# board.net
KiCad netlist of a schematic drawn in EAGLE
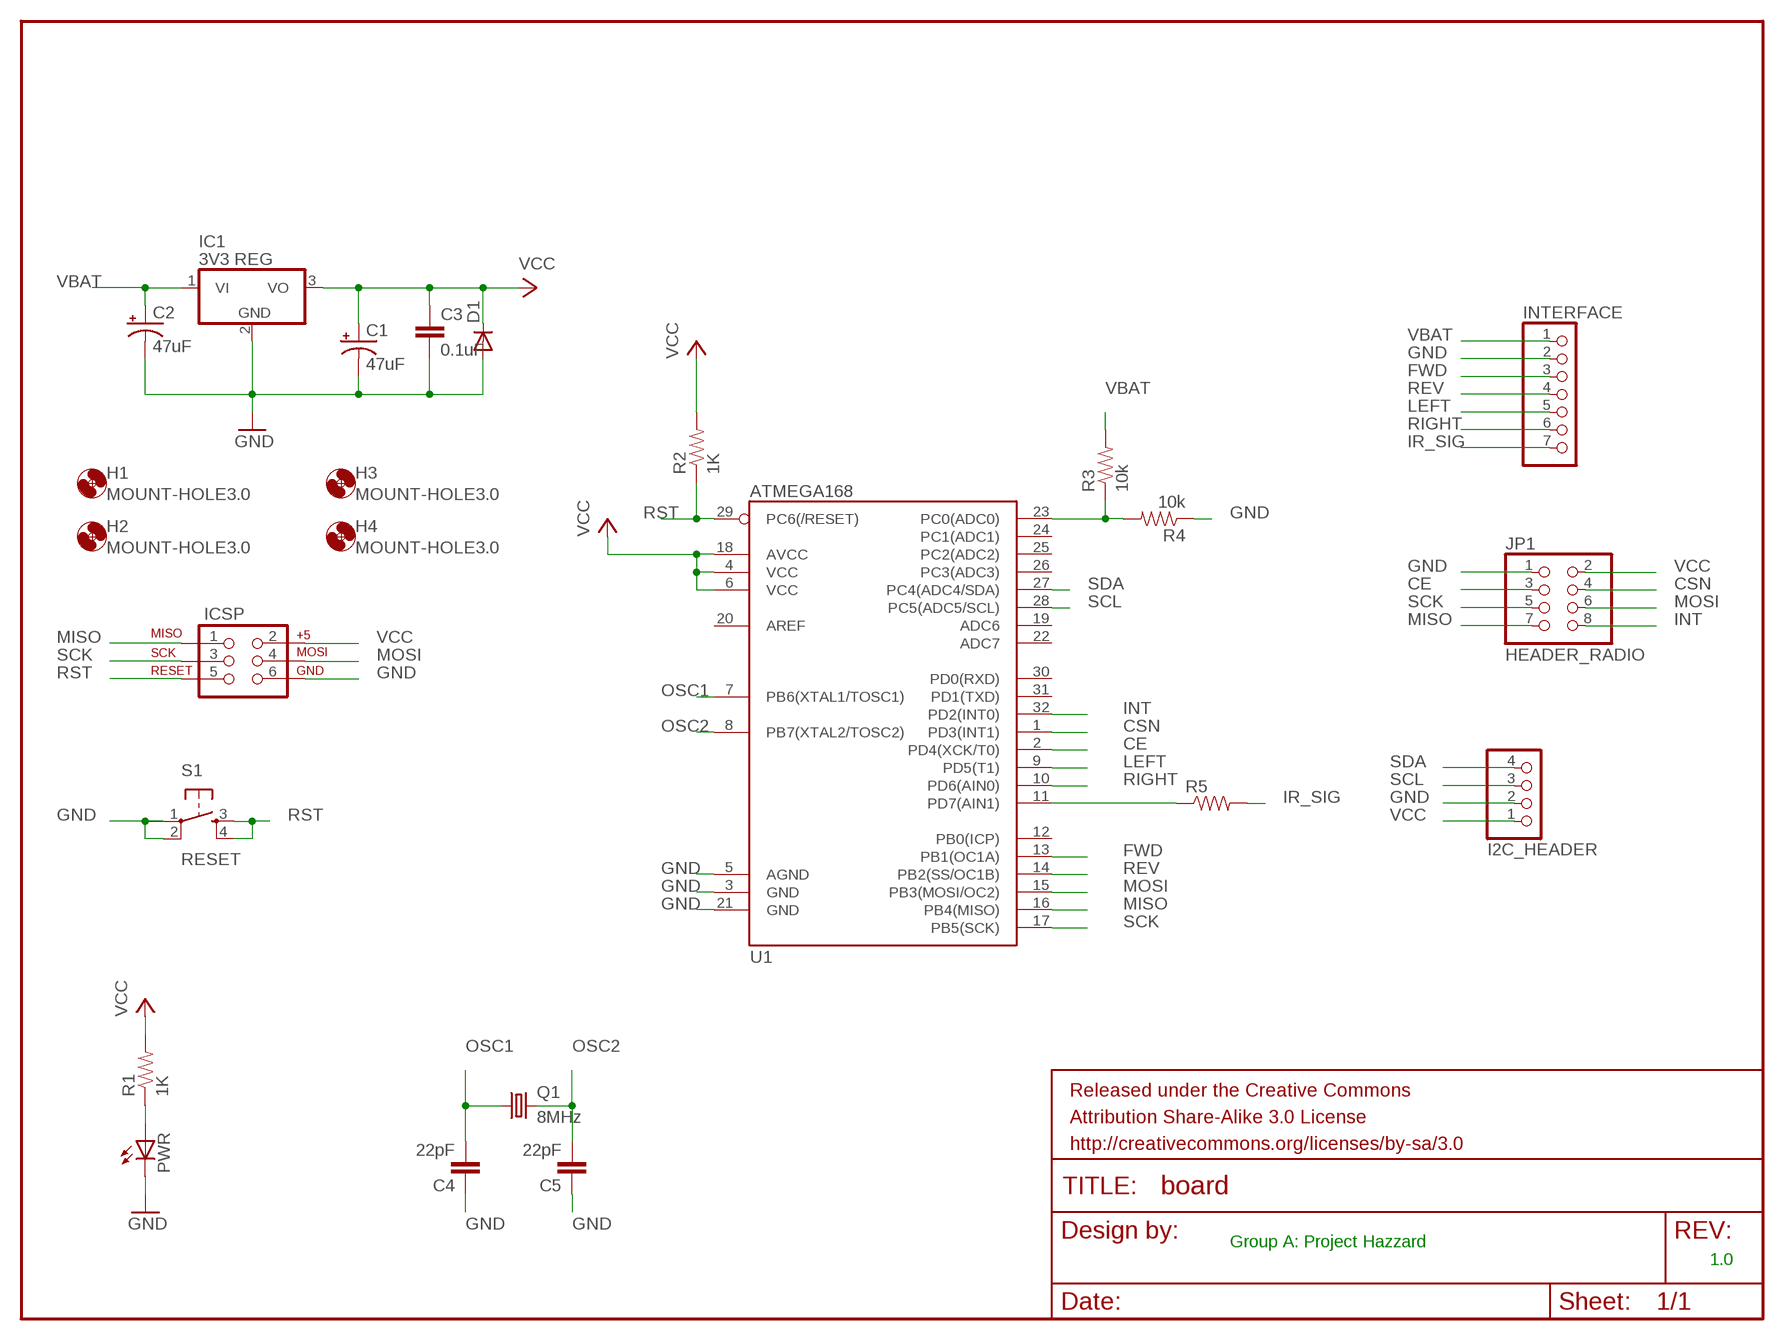
[diagram p0: schematic, sheet 1]

(export (version "E")
  (design (tool "Eeschema 10.0.6"))
  (components
    (comp (ref "C1")
      (value "47uF")
      (footprint "eagle-import:CPOL-RADIAL-100UF-25V")
      (libsource (lib "eagle-import") (part "CAP_POLPTH1"))
    )
    (comp (ref "C2")
      (value "47uF")
      (footprint "eagle-import:CPOL-RADIAL-100UF-25V")
      (libsource (lib "eagle-import") (part "CAP_POLPTH1"))
    )
    (comp (ref "C3")
      (value "0.1uF")
      (footprint "eagle-import:CAP-PTH-SMALL-KIT")
      (libsource (lib "eagle-import") (part "CAPKIT"))
    )
    (comp (ref "C4")
      (value "22pF")
      (footprint "eagle-import:CAP-PTH-SMALL")
      (libsource (lib "eagle-import") (part "CAPPTH"))
    )
    (comp (ref "C5")
      (value "22pF")
      (footprint "eagle-import:CAP-PTH-SMALL")
      (libsource (lib "eagle-import") (part "CAPPTH"))
    )
    (comp (ref "D1")
      (value "DIODEPTH")
      (footprint "eagle-import:DIODE-1N4001")
      (libsource (lib "eagle-import") (part "DIODEPTH"))
    )
    (comp (ref "FRAME1")
      (value "FRAME-LETTER")
      (footprint "eagle-import:CREATIVE_COMMONS")
      (libsource (lib "eagle-import") (part "FRAME-LETTER"))
    )
    (comp (ref "H1")
      (value "MOUNT-HOLE3.0")
      (footprint "eagle-import:3,0")
      (libsource (lib "eagle-import") (part "MOUNT-HOLE3.0"))
    )
    (comp (ref "H2")
      (value "MOUNT-HOLE3.0")
      (footprint "eagle-import:3,0")
      (libsource (lib "eagle-import") (part "MOUNT-HOLE3.0"))
    )
    (comp (ref "H3")
      (value "MOUNT-HOLE3.0")
      (footprint "eagle-import:3,0")
      (libsource (lib "eagle-import") (part "MOUNT-HOLE3.0"))
    )
    (comp (ref "H4")
      (value "MOUNT-HOLE3.0")
      (footprint "eagle-import:3,0")
      (libsource (lib "eagle-import") (part "MOUNT-HOLE3.0"))
    )
    (comp (ref "I2C_HEADER")
      (value "PINHD-1X4")
      (footprint "eagle-import:1X04")
      (libsource (lib "eagle-import") (part "PINHD-1X4"))
    )
    (comp (ref "IC1")
      (value "3V3 REG")
      (footprint "eagle-import:TO220V")
      (libsource (lib "eagle-import") (part "78TV6"))
    )
    (comp (ref "ICSP")
      (value "AVR_SPI_PRG_6PTH")
      (footprint "eagle-import:2X3")
      (libsource (lib "eagle-import") (part "AVR_SPI_PRG_6PTH"))
    )
    (comp (ref "INTERFACE")
      (value "PINHD-1X7")
      (footprint "eagle-import:1X07")
      (libsource (lib "eagle-import") (part "PINHD-1X7"))
    )
    (comp (ref "JP1")
      (value "HEADER_RADIO")
      (footprint "eagle-import:2X04")
      (libsource (lib "eagle-import") (part "PINHD-2X4"))
    )
    (comp (ref "PWR")
      (value "LED5MM")
      (footprint "eagle-import:LED5MM")
      (libsource (lib "eagle-import") (part "LED5MM"))
    )
    (comp (ref "Q1")
      (value "8MHz")
      (footprint "eagle-import:HC49_S")
      (libsource (lib "eagle-import") (part "CRYSTALHC49S"))
    )
    (comp (ref "R1")
      (value "1K")
      (footprint "eagle-import:AXIAL-0.4")
      (libsource (lib "eagle-import") (part "RESISTORPTH-1/4W"))
    )
    (comp (ref "R2")
      (value "1K")
      (footprint "eagle-import:AXIAL-0.4")
      (libsource (lib "eagle-import") (part "RESISTORPTH-1/4W"))
    )
    (comp (ref "R3")
      (value "10k")
      (footprint "eagle-import:AXIAL-0.4")
      (libsource (lib "eagle-import") (part "SparkFun-Passives_RESISTORPTH-1/4W"))
    )
    (comp (ref "R4")
      (value "10k")
      (footprint "eagle-import:AXIAL-0.4")
      (libsource (lib "eagle-import") (part "SparkFun-Passives_RESISTORPTH-1/4W"))
    )
    (comp (ref "R5")
      (value "RESISTORPTH-1/4W")
      (footprint "eagle-import:AXIAL-0.4")
      (libsource (lib "eagle-import") (part "SparkFun-Passives_RESISTORPTH-1/4W"))
    )
    (comp (ref "S1")
      (value "RESET")
      (footprint "eagle-import:TACTILE-PTH")
      (libsource (lib "eagle-import") (part "TAC_SWITCHPTH"))
    )
    (comp (ref "U1")
      (value "ATMEGA168")
      (footprint "eagle-import:TQFP32-08")
      (libsource (lib "eagle-import") (part "ATMEGA168"))
    )
  )
  (nets
    (net (code "1") (name "/CE") (class "Default")
      (node (ref "JP1") (pin "3") (pinfunction "3_3") (pintype "passive"))
      (node (ref "U1") (pin "2") (pinfunction "PD4(XCK/T0)_2") (pintype "bidirectional"))
    )
    (net (code "2") (name "/CSN") (class "Default")
      (node (ref "JP1") (pin "4") (pinfunction "4_4") (pintype "passive"))
      (node (ref "U1") (pin "1") (pinfunction "PD3(INT1)_1") (pintype "bidirectional"))
    )
    (net (code "3") (name "/FWD") (class "Default")
      (node (ref "INTERFACE") (pin "3") (pinfunction "3_3") (pintype "passive"))
      (node (ref "U1") (pin "13") (pinfunction "PB1(OC1A)_13") (pintype "bidirectional"))
    )
    (net (code "4") (name "/INT") (class "Default")
      (node (ref "JP1") (pin "8") (pinfunction "8_8") (pintype "passive"))
      (node (ref "U1") (pin "32") (pinfunction "PD2(INT0)_32") (pintype "bidirectional"))
    )
    (net (code "5") (name "/IR_SIG") (class "Default")
      (node (ref "INTERFACE") (pin "7") (pinfunction "7_7") (pintype "passive"))
      (node (ref "R5") (pin "P$2") (pinfunction "2_P$2") (pintype "passive"))
    )
    (net (code "6") (name "/LEFT") (class "Default")
      (node (ref "INTERFACE") (pin "5") (pinfunction "5_5") (pintype "passive"))
      (node (ref "U1") (pin "9") (pinfunction "PD5(T1)_9") (pintype "bidirectional"))
    )
    (net (code "7") (name "/MISO") (class "Default")
      (node (ref "ICSP") (pin "1") (pinfunction "1_1") (pintype "passive"))
      (node (ref "JP1") (pin "7") (pinfunction "7_7") (pintype "passive"))
      (node (ref "U1") (pin "16") (pinfunction "PB4(MISO)_16") (pintype "bidirectional"))
    )
    (net (code "8") (name "/MOSI") (class "Default")
      (node (ref "ICSP") (pin "4") (pinfunction "4_4") (pintype "passive"))
      (node (ref "JP1") (pin "6") (pinfunction "6_6") (pintype "passive"))
      (node (ref "U1") (pin "15") (pinfunction "PB3(MOSI/OC2)_15") (pintype "bidirectional"))
    )
    (net (code "9") (name "/OSC1") (class "Default")
      (node (ref "C4") (pin "2") (pinfunction "2_2") (pintype "passive"))
      (node (ref "Q1") (pin "1") (pinfunction "1_1") (pintype "passive"))
      (node (ref "U1") (pin "7") (pinfunction "PB6(XTAL1/TOSC1)_7") (pintype "bidirectional"))
    )
    (net (code "10") (name "/OSC2") (class "Default")
      (node (ref "C5") (pin "2") (pinfunction "2_2") (pintype "passive"))
      (node (ref "Q1") (pin "2") (pinfunction "2_2") (pintype "passive"))
      (node (ref "U1") (pin "8") (pinfunction "PB7(XTAL2/TOSC2)_8") (pintype "bidirectional"))
    )
    (net (code "11") (name "/REV") (class "Default")
      (node (ref "INTERFACE") (pin "4") (pinfunction "4_4") (pintype "passive"))
      (node (ref "U1") (pin "14") (pinfunction "PB2(SS/OC1B)_14") (pintype "bidirectional"))
    )
    (net (code "12") (name "/RIGHT") (class "Default")
      (node (ref "INTERFACE") (pin "6") (pinfunction "6_6") (pintype "passive"))
      (node (ref "U1") (pin "10") (pinfunction "PD6(AIN0)_10") (pintype "bidirectional"))
    )
    (net (code "13") (name "/RST") (class "Default")
      (node (ref "ICSP") (pin "5") (pinfunction "5_5") (pintype "passive"))
      (node (ref "R2") (pin "P$1") (pinfunction "1_P$1") (pintype "passive"))
      (node (ref "S1") (pin "3") (pinfunction "3_3") (pintype "passive"))
      (node (ref "S1") (pin "4") (pinfunction "4_4") (pintype "passive"))
      (node (ref "U1") (pin "29") (pinfunction "PC6(/RESET)_29") (pintype "bidirectional"))
    )
    (net (code "14") (name "/SCK") (class "Default")
      (node (ref "ICSP") (pin "3") (pinfunction "3_3") (pintype "passive"))
      (node (ref "JP1") (pin "5") (pinfunction "5_5") (pintype "passive"))
      (node (ref "U1") (pin "17") (pinfunction "PB5(SCK)_17") (pintype "bidirectional"))
    )
    (net (code "15") (name "/SCL") (class "Default")
      (node (ref "I2C_HEADER") (pin "3") (pinfunction "3_3") (pintype "passive"))
      (node (ref "U1") (pin "28") (pinfunction "PC5(ADC5/SCL)_28") (pintype "bidirectional"))
    )
    (net (code "16") (name "/SDA") (class "Default")
      (node (ref "I2C_HEADER") (pin "4") (pinfunction "4_4") (pintype "passive"))
      (node (ref "U1") (pin "27") (pinfunction "PC4(ADC4/SDA)_27") (pintype "bidirectional"))
    )
    (net (code "17") (name "/VBAT") (class "Default")
      (node (ref "C2") (pin "1") (pinfunction "+_1") (pintype "passive"))
      (node (ref "IC1") (pin "1") (pinfunction "VI_1") (pintype "input"))
      (node (ref "INTERFACE") (pin "1") (pinfunction "1_1") (pintype "passive"))
      (node (ref "R3") (pin "P$2") (pinfunction "2_P$2") (pintype "passive"))
    )
    (net (code "18") (name "GND") (class "Default")
      (node (ref "C1") (pin "2") (pinfunction "-_2") (pintype "passive"))
      (node (ref "C2") (pin "2") (pinfunction "-_2") (pintype "passive"))
      (node (ref "C3") (pin "2") (pinfunction "2_2") (pintype "passive"))
      (node (ref "C4") (pin "1") (pinfunction "1_1") (pintype "passive"))
      (node (ref "C5") (pin "1") (pinfunction "1_1") (pintype "passive"))
      (node (ref "D1") (pin "A") (pinfunction "A_A") (pintype "passive"))
      (node (ref "I2C_HEADER") (pin "2") (pinfunction "2_2") (pintype "passive"))
      (node (ref "IC1") (pin "2") (pinfunction "GND_2") (pintype "passive"))
      (node (ref "ICSP") (pin "6") (pinfunction "6_6") (pintype "passive"))
      (node (ref "INTERFACE") (pin "2") (pinfunction "2_2") (pintype "passive"))
      (node (ref "JP1") (pin "1") (pinfunction "1_1") (pintype "passive"))
      (node (ref "PWR") (pin "K") (pinfunction "C_K") (pintype "passive"))
      (node (ref "R4") (pin "P$1") (pinfunction "1_P$1") (pintype "passive"))
      (node (ref "S1") (pin "1") (pinfunction "1_1") (pintype "passive"))
      (node (ref "S1") (pin "2") (pinfunction "2_2") (pintype "passive"))
      (node (ref "U1") (pin "21") (pinfunction "GND_21") (pintype "bidirectional"))
      (node (ref "U1") (pin "3") (pinfunction "GND_3") (pintype "bidirectional"))
      (node (ref "U1") (pin "5") (pinfunction "AGND_5") (pintype "bidirectional"))
    )
    (net (code "19") (name "Net-(R1-1)") (class "Default")
      (node (ref "PWR") (pin "A") (pinfunction "A_A") (pintype "passive"))
      (node (ref "R1") (pin "P$1") (pinfunction "1_P$1") (pintype "passive"))
    )
    (net (code "20") (name "Net-(R3-1)") (class "Default")
      (node (ref "R3") (pin "P$1") (pinfunction "1_P$1") (pintype "passive"))
      (node (ref "R4") (pin "P$2") (pinfunction "2_P$2") (pintype "passive"))
      (node (ref "U1") (pin "23") (pinfunction "PC0(ADC0)_23") (pintype "bidirectional"))
    )
    (net (code "21") (name "Net-(R5-1)") (class "Default")
      (node (ref "R5") (pin "P$1") (pinfunction "1_P$1") (pintype "passive"))
      (node (ref "U1") (pin "11") (pinfunction "PD7(AIN1)_11") (pintype "bidirectional"))
    )
    (net (code "22") (name "VCC") (class "Default")
      (node (ref "C1") (pin "1") (pinfunction "+_1") (pintype "passive"))
      (node (ref "C3") (pin "1") (pinfunction "1_1") (pintype "passive"))
      (node (ref "D1") (pin "C") (pinfunction "C_C") (pintype "passive"))
      (node (ref "I2C_HEADER") (pin "1") (pinfunction "1_1") (pintype "passive"))
      (node (ref "IC1") (pin "3") (pinfunction "VO_3") (pintype "passive"))
      (node (ref "ICSP") (pin "2") (pinfunction "2_2") (pintype "passive"))
      (node (ref "JP1") (pin "2") (pinfunction "2_2") (pintype "passive"))
      (node (ref "R1") (pin "P$2") (pinfunction "2_P$2") (pintype "passive"))
      (node (ref "R2") (pin "P$2") (pinfunction "2_P$2") (pintype "passive"))
      (node (ref "U1") (pin "18") (pinfunction "AVCC_18") (pintype "bidirectional"))
      (node (ref "U1") (pin "4") (pinfunction "VCC_4") (pintype "bidirectional"))
      (node (ref "U1") (pin "6") (pinfunction "VCC_6") (pintype "bidirectional"))
    )
    (net (code "23") (name "unconnected-(U1-ADC6-Pad19)") (class "Default")
      (node (ref "U1") (pin "19") (pinfunction "ADC6_19") (pintype "bidirectional"))
    )
    (net (code "24") (name "unconnected-(U1-ADC7-Pad22)") (class "Default")
      (node (ref "U1") (pin "22") (pinfunction "ADC7_22") (pintype "bidirectional"))
    )
    (net (code "25") (name "unconnected-(U1-AREF-Pad20)") (class "Default")
      (node (ref "U1") (pin "20") (pinfunction "AREF_20") (pintype "bidirectional"))
    )
    (net (code "26") (name "unconnected-(U1-PB0(ICP)-Pad12)") (class "Default")
      (node (ref "U1") (pin "12") (pinfunction "PB0(ICP)_12") (pintype "bidirectional"))
    )
    (net (code "27") (name "unconnected-(U1-PC1(ADC1)-Pad24)") (class "Default")
      (node (ref "U1") (pin "24") (pinfunction "PC1(ADC1)_24") (pintype "bidirectional"))
    )
    (net (code "28") (name "unconnected-(U1-PC2(ADC2)-Pad25)") (class "Default")
      (node (ref "U1") (pin "25") (pinfunction "PC2(ADC2)_25") (pintype "bidirectional"))
    )
    (net (code "29") (name "unconnected-(U1-PC3(ADC3)-Pad26)") (class "Default")
      (node (ref "U1") (pin "26") (pinfunction "PC3(ADC3)_26") (pintype "bidirectional"))
    )
    (net (code "30") (name "unconnected-(U1-PD0(RXD)-Pad30)") (class "Default")
      (node (ref "U1") (pin "30") (pinfunction "PD0(RXD)_30") (pintype "bidirectional"))
    )
    (net (code "31") (name "unconnected-(U1-PD1(TXD)-Pad31)") (class "Default")
      (node (ref "U1") (pin "31") (pinfunction "PD1(TXD)_31") (pintype "bidirectional"))
    )
  )
)
